# UNIDOCK_SIMPLE_2020-10-20_22-44-49.net
KiCad netlist of a schematic drawn in Altium Designer
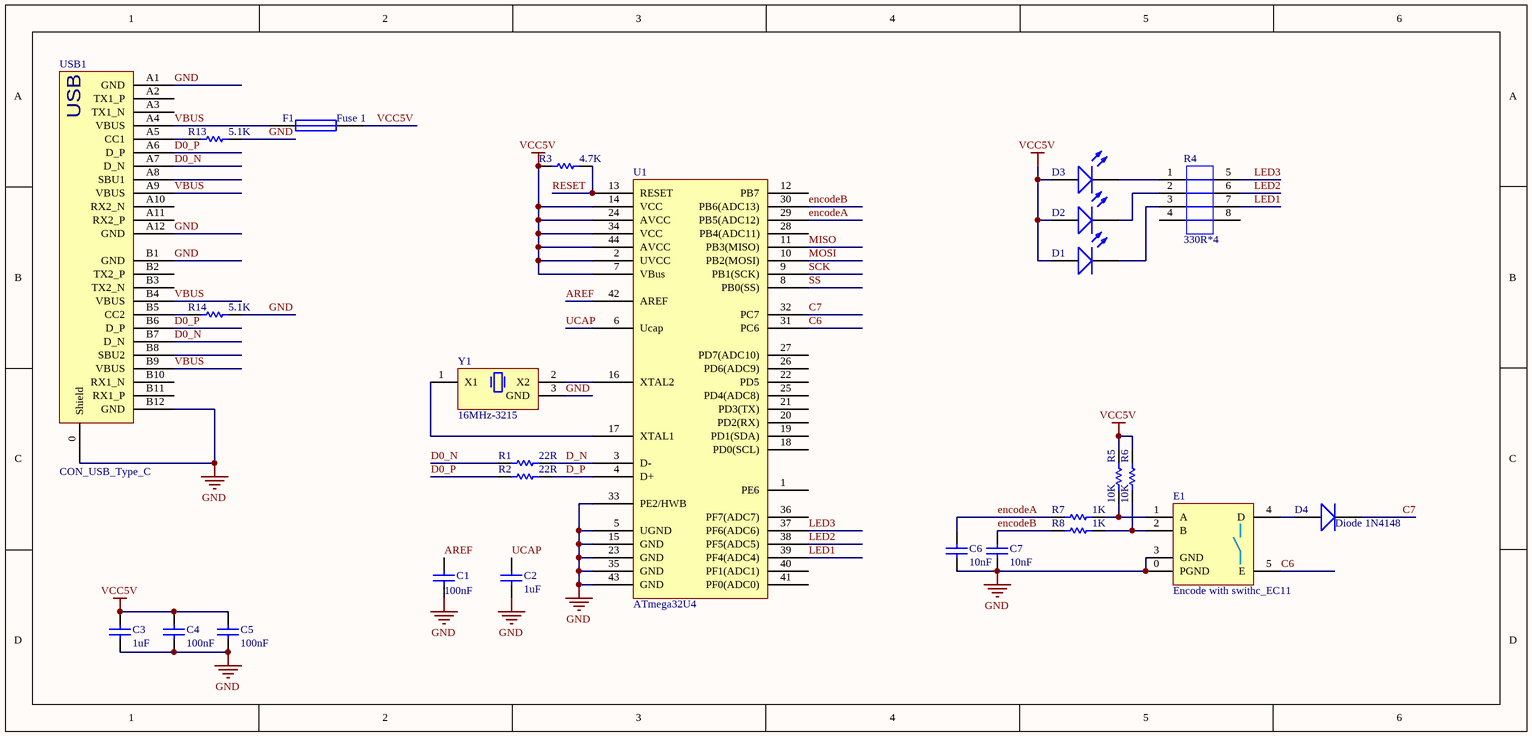
[diagram p0: UNIDOCK SIMPLE_2020-10-20_22-44-49.schdoc]

(export (version "E")
  (design (tool "Eeschema 10.0.6"))
  (components
    (comp (ref "C1")
      (value "100nF")
      (fields (field (name "PUBLISHER") "Altium Limited"))
      (libsource (lib "altium-import") (part "root_1_100nF_"))
    )
    (comp (ref "C2")
      (value "1uF")
      (fields (field (name "PUBLISHER") "Altium Limited"))
      (libsource (lib "altium-import") (part "root_3_1uF_"))
    )
    (comp (ref "C3")
      (value "1uF")
      (fields (field (name "PUBLISHER") "Altium Limited"))
      (libsource (lib "altium-import") (part "root_3_1uF_"))
    )
    (comp (ref "C4")
      (value "100nF")
      (fields (field (name "PUBLISHER") "Altium Limited"))
      (libsource (lib "altium-import") (part "root_3_100nF_"))
    )
    (comp (ref "C5")
      (value "100nF")
      (fields (field (name "PUBLISHER") "Altium Limited"))
      (libsource (lib "altium-import") (part "root_3_100nF_"))
    )
    (comp (ref "C6")
      (value "10nF")
      (fields (field (name "PUBLISHER") "Altium Limited"))
      (libsource (lib "altium-import") (part "root_1_10nF_"))
    )
    (comp (ref "C7")
      (value "10nF")
      (fields (field (name "PUBLISHER") "Altium Limited"))
      (libsource (lib "altium-import") (part "root_1_10nF_"))
    )
    (comp (ref "D1")
      (value "LED0")
      (fields (field (name "PUBLISHER") "Altium Limited"))
      (libsource (lib "altium-import") (part "root_0_LED0_"))
    )
    (comp (ref "D2")
      (value "LED0")
      (fields (field (name "PUBLISHER") "Altium Limited"))
      (libsource (lib "altium-import") (part "root_0_LED0_"))
    )
    (comp (ref "D3")
      (value "LED0")
      (fields (field (name "PUBLISHER") "Altium Limited"))
      (libsource (lib "altium-import") (part "root_0_LED0_"))
    )
    (comp (ref "D4")
      (value "Diode 1N4148")
      (fields (field (name "PUBLISHER") "Altium Limited"))
      (libsource (lib "altium-import") (part "root_0_Diode 1N4148_"))
    )
    (comp (ref "E1")
      (value "Encode with swithc_EC11")
      (libsource (lib "altium-import") (part "root_0_Encode with swithc_EC11_"))
    )
    (comp (ref "F1")
      (value "Fuse 1")
      (fields (field (name "PUBLISHER") "Altium Limited"))
      (libsource (lib "altium-import") (part "root_0_Fuse 1_"))
    )
    (comp (ref "R1")
      (value "22R")
      (fields (field (name "PUBLISHER") "Altium Limited"))
      (libsource (lib "altium-import") (part "root_2_22R_"))
    )
    (comp (ref "R2")
      (value "22R")
      (fields (field (name "PUBLISHER") "Altium Limited"))
      (libsource (lib "altium-import") (part "root_2_22R_"))
    )
    (comp (ref "R3")
      (value "4.7K")
      (fields (field (name "PUBLISHER") "Altium Limited"))
      (libsource (lib "altium-import") (part "root_0_4.7K_"))
    )
    (comp (ref "R4") (value "330R*4") (libsource (lib "altium-import") (part "root_0_330R*4_")))
    (comp (ref "R5")
      (value "10K")
      (fields (field (name "PUBLISHER") "Altium Limited"))
      (libsource (lib "altium-import") (part "root_1_10K_"))
    )
    (comp (ref "R6")
      (value "10K")
      (fields (field (name "PUBLISHER") "Altium Limited"))
      (libsource (lib "altium-import") (part "root_1_10K_"))
    )
    (comp (ref "R7")
      (value "1K")
      (fields (field (name "PUBLISHER") "Altium Limited"))
      (libsource (lib "altium-import") (part "root_0_1K_"))
    )
    (comp (ref "R8")
      (value "1K")
      (fields (field (name "PUBLISHER") "Altium Limited"))
      (libsource (lib "altium-import") (part "root_0_1K_"))
    )
    (comp (ref "R13")
      (value "5.1K")
      (fields (field (name "PUBLISHER") "Altium Limited"))
      (libsource (lib "altium-import") (part "root_0_5.1K_"))
    )
    (comp (ref "R14")
      (value "5.1K")
      (fields (field (name "PUBLISHER") "Altium Limited"))
      (libsource (lib "altium-import") (part "root_0_5.1K_"))
    )
    (comp (ref "U1") (value "ATmega32U4") (libsource (lib "altium-import") (part "root_0_ATmega32U4_")))
    (comp (ref "USB1")
      (value "CON_USB_Type_C")
      (libsource (lib "altium-import") (part "root_0_CON_USB_Type_C_"))
    )
    (comp (ref "Y1") (value "16MHz-3215") (libsource (lib "altium-import") (part "root_0_16MHz-3215_")))
  )
  (nets
    (net (code "1") (name "/AREF") (class "Default")
      (node (ref "C1") (pin "2") (pinfunction "2_2") (pintype "passive"))
      (node (ref "U1") (pin "42") (pinfunction "AREF_42") (pintype "passive"))
    )
    (net (code "2") (name "/C6") (class "Default")
      (node (ref "E1") (pin "5") (pinfunction "E_5") (pintype "passive"))
      (node (ref "U1") (pin "31") (pinfunction "PC6_31") (pintype "passive"))
    )
    (net (code "3") (name "/C7") (class "Default")
      (node (ref "D4") (pin "2") (pinfunction "K_2") (pintype "passive"))
      (node (ref "U1") (pin "32") (pinfunction "PC7_32") (pintype "passive"))
    )
    (net (code "4") (name "/D0_N") (class "Default")
      (node (ref "R1") (pin "2") (pinfunction "2_2") (pintype "passive"))
      (node (ref "USB1") (pin "A7") (pinfunction "D_N_A7") (pintype "passive"))
      (node (ref "USB1") (pin "B7") (pinfunction "D_N_B7") (pintype "passive"))
    )
    (net (code "5") (name "/D0_P") (class "Default")
      (node (ref "R2") (pin "2") (pinfunction "2_2") (pintype "passive"))
      (node (ref "USB1") (pin "A6") (pinfunction "D_P_A6") (pintype "passive"))
      (node (ref "USB1") (pin "B6") (pinfunction "D_P_B6") (pintype "passive"))
    )
    (net (code "6") (name "/D_N") (class "Default")
      (node (ref "R1") (pin "1") (pinfunction "1_1") (pintype "passive"))
      (node (ref "U1") (pin "3") (pinfunction "D-_3") (pintype "passive"))
    )
    (net (code "7") (name "/D_P") (class "Default")
      (node (ref "R2") (pin "1") (pinfunction "1_1") (pintype "passive"))
      (node (ref "U1") (pin "4") (pinfunction "D+_4") (pintype "passive"))
    )
    (net (code "8") (name "/LED1") (class "Default")
      (node (ref "R4") (pin "7") (pinfunction "7_7") (pintype "passive"))
      (node (ref "U1") (pin "39") (pinfunction "PF4(ADC4)_39") (pintype "passive"))
    )
    (net (code "9") (name "/LED2") (class "Default")
      (node (ref "R4") (pin "6") (pinfunction "6_6") (pintype "passive"))
      (node (ref "U1") (pin "38") (pinfunction "PF5(ADC5)_38") (pintype "passive"))
    )
    (net (code "10") (name "/LED3") (class "Default")
      (node (ref "R4") (pin "5") (pinfunction "5_5") (pintype "passive"))
      (node (ref "U1") (pin "37") (pinfunction "PF6(ADC6)_37") (pintype "passive"))
    )
    (net (code "11") (name "/MISO") (class "Default")
      (node (ref "U1") (pin "11") (pinfunction "PB3(MISO)_11") (pintype "passive"))
    )
    (net (code "12") (name "/MOSI") (class "Default")
      (node (ref "U1") (pin "10") (pinfunction "PB2(MOSI)_10") (pintype "passive"))
    )
    (net (code "13") (name "/RESET") (class "Default")
      (node (ref "R3") (pin "2") (pinfunction "2_2") (pintype "passive"))
      (node (ref "U1") (pin "13") (pinfunction "RESET_13") (pintype "passive"))
    )
    (net (code "14") (name "/SCK") (class "Default")
      (node (ref "U1") (pin "9") (pinfunction "PB1(SCK)_9") (pintype "passive"))
    )
    (net (code "15") (name "/SS") (class "Default")
      (node (ref "U1") (pin "8") (pinfunction "PB0(SS)_8") (pintype "passive"))
    )
    (net (code "16") (name "/UCAP") (class "Default")
      (node (ref "C2") (pin "1") (pinfunction "1_1") (pintype "passive"))
      (node (ref "U1") (pin "6") (pinfunction "Ucap_6") (pintype "passive"))
    )
    (net (code "17") (name "/VBUS") (class "Default")
      (node (ref "F1") (pin "1") (pinfunction "1_1") (pintype "passive"))
      (node (ref "USB1") (pin "A4") (pinfunction "VBUS_A4") (pintype "passive"))
      (node (ref "USB1") (pin "A9") (pinfunction "VBUS_A9") (pintype "passive"))
      (node (ref "USB1") (pin "B4") (pinfunction "VBUS_B4") (pintype "passive"))
      (node (ref "USB1") (pin "B9") (pinfunction "VBUS_B9") (pintype "passive"))
    )
    (net (code "18") (name "/encodeA") (class "Default")
      (node (ref "C6") (pin "2") (pinfunction "2_2") (pintype "passive"))
      (node (ref "R7") (pin "1") (pinfunction "1_1") (pintype "passive"))
      (node (ref "U1") (pin "29") (pinfunction "PB5(ADC12)_29") (pintype "passive"))
    )
    (net (code "19") (name "/encodeB") (class "Default")
      (node (ref "C7") (pin "2") (pinfunction "2_2") (pintype "passive"))
      (node (ref "R8") (pin "1") (pinfunction "1_1") (pintype "passive"))
      (node (ref "U1") (pin "30") (pinfunction "PB6(ADC13)_30") (pintype "passive"))
    )
    (net (code "20") (name "GND") (class "Default")
      (node (ref "C1") (pin "1") (pinfunction "1_1") (pintype "passive"))
      (node (ref "C2") (pin "2") (pinfunction "2_2") (pintype "passive"))
      (node (ref "C3") (pin "2") (pinfunction "2_2") (pintype "passive"))
      (node (ref "C4") (pin "2") (pinfunction "2_2") (pintype "passive"))
      (node (ref "C5") (pin "2") (pinfunction "2_2") (pintype "passive"))
      (node (ref "C6") (pin "1") (pinfunction "1_1") (pintype "passive"))
      (node (ref "C7") (pin "1") (pinfunction "1_1") (pintype "passive"))
      (node (ref "E1") (pin "0") (pinfunction "PGND_0") (pintype "passive"))
      (node (ref "E1") (pin "3") (pinfunction "GND_3") (pintype "passive"))
      (node (ref "R13") (pin "2") (pinfunction "2_2") (pintype "passive"))
      (node (ref "R14") (pin "2") (pinfunction "2_2") (pintype "passive"))
      (node (ref "U1") (pin "15") (pinfunction "GND_15") (pintype "passive"))
      (node (ref "U1") (pin "23") (pinfunction "GND_23") (pintype "passive"))
      (node (ref "U1") (pin "33") (pinfunction "PE2/HWB_33") (pintype "passive"))
      (node (ref "U1") (pin "35") (pinfunction "GND_35") (pintype "passive"))
      (node (ref "U1") (pin "43") (pinfunction "GND_43") (pintype "passive"))
      (node (ref "U1") (pin "5") (pinfunction "UGND_5") (pintype "passive"))
      (node (ref "USB1") (pin "0") (pinfunction "Shield_0") (pintype "passive"))
      (node (ref "USB1") (pin "A1") (pinfunction "GND_A1") (pintype "passive"))
      (node (ref "USB1") (pin "A12") (pinfunction "GND_A12") (pintype "passive"))
      (node (ref "USB1") (pin "B1") (pinfunction "GND_B1") (pintype "passive"))
      (node (ref "USB1") (pin "B12") (pinfunction "GND_B12") (pintype "passive"))
      (node (ref "Y1") (pin "3") (pinfunction "GND_3") (pintype "passive"))
    )
    (net (code "21") (name "Net-(D1-K)") (class "Default")
      (node (ref "D1") (pin "2") (pinfunction "K_2") (pintype "passive"))
      (node (ref "R4") (pin "3") (pinfunction "3_3") (pintype "passive"))
    )
    (net (code "22") (name "Net-(D2-K)") (class "Default")
      (node (ref "D2") (pin "2") (pinfunction "K_2") (pintype "passive"))
      (node (ref "R4") (pin "2") (pinfunction "2_2") (pintype "passive"))
    )
    (net (code "23") (name "Net-(D3-K)") (class "Default")
      (node (ref "D3") (pin "2") (pinfunction "K_2") (pintype "passive"))
      (node (ref "R4") (pin "1") (pinfunction "1_1") (pintype "passive"))
    )
    (net (code "24") (name "Net-(D4-A)") (class "Default")
      (node (ref "D4") (pin "1") (pinfunction "A_1") (pintype "passive"))
      (node (ref "E1") (pin "4") (pinfunction "D_4") (pintype "passive"))
    )
    (net (code "25") (name "Net-(E1-A)") (class "Default")
      (node (ref "E1") (pin "1") (pinfunction "A_1") (pintype "passive"))
      (node (ref "R5") (pin "1") (pinfunction "1_1") (pintype "passive"))
      (node (ref "R7") (pin "2") (pinfunction "2_2") (pintype "passive"))
    )
    (net (code "26") (name "Net-(E1-B)") (class "Default")
      (node (ref "E1") (pin "2") (pinfunction "B_2") (pintype "passive"))
      (node (ref "R6") (pin "1") (pinfunction "1_1") (pintype "passive"))
      (node (ref "R8") (pin "2") (pinfunction "2_2") (pintype "passive"))
    )
    (net (code "27") (name "Net-(U1-XTAL1)") (class "Default")
      (node (ref "U1") (pin "17") (pinfunction "XTAL1_17") (pintype "passive"))
      (node (ref "Y1") (pin "1") (pinfunction "X1_1") (pintype "passive"))
    )
    (net (code "28") (name "Net-(U1-XTAL2)") (class "Default")
      (node (ref "U1") (pin "16") (pinfunction "XTAL2_16") (pintype "passive"))
      (node (ref "Y1") (pin "2") (pinfunction "X2_2") (pintype "passive"))
    )
    (net (code "29") (name "Net-(USB1-CC1)") (class "Default")
      (node (ref "R13") (pin "1") (pinfunction "1_1") (pintype "passive"))
      (node (ref "USB1") (pin "A5") (pinfunction "CC1_A5") (pintype "passive"))
    )
    (net (code "30") (name "Net-(USB1-CC2)") (class "Default")
      (node (ref "R14") (pin "1") (pinfunction "1_1") (pintype "passive"))
      (node (ref "USB1") (pin "B5") (pinfunction "CC2_B5") (pintype "passive"))
    )
    (net (code "31") (name "VCC5V") (class "Default")
      (node (ref "C3") (pin "1") (pinfunction "1_1") (pintype "passive"))
      (node (ref "C4") (pin "1") (pinfunction "1_1") (pintype "passive"))
      (node (ref "C5") (pin "1") (pinfunction "1_1") (pintype "passive"))
      (node (ref "D1") (pin "1") (pinfunction "A_1") (pintype "passive"))
      (node (ref "D2") (pin "1") (pinfunction "A_1") (pintype "passive"))
      (node (ref "D3") (pin "1") (pinfunction "A_1") (pintype "passive"))
      (node (ref "F1") (pin "2") (pinfunction "2_2") (pintype "passive"))
      (node (ref "R3") (pin "1") (pinfunction "1_1") (pintype "passive"))
      (node (ref "R5") (pin "2") (pinfunction "2_2") (pintype "passive"))
      (node (ref "R6") (pin "2") (pinfunction "2_2") (pintype "passive"))
      (node (ref "U1") (pin "14") (pinfunction "VCC_14") (pintype "passive"))
      (node (ref "U1") (pin "2") (pinfunction "UVCC_2") (pintype "passive"))
      (node (ref "U1") (pin "24") (pinfunction "AVCC_24") (pintype "passive"))
      (node (ref "U1") (pin "34") (pinfunction "VCC_34") (pintype "passive"))
      (node (ref "U1") (pin "44") (pinfunction "AVCC_44") (pintype "passive"))
      (node (ref "U1") (pin "7") (pinfunction "VBus_7") (pintype "passive"))
    )
    (net (code "32") (name "unconnected-(R4-Pad4)") (class "Default")
      (node (ref "R4") (pin "4") (pinfunction "4_4") (pintype "passive"))
    )
    (net (code "33") (name "unconnected-(R4-Pad8)") (class "Default")
      (node (ref "R4") (pin "8") (pinfunction "8_8") (pintype "passive"))
    )
    (net (code "34") (name "unconnected-(U1-PB4(ADC11)-Pad28)") (class "Default")
      (node (ref "U1") (pin "28") (pinfunction "PB4(ADC11)_28") (pintype "passive"))
    )
    (net (code "35") (name "unconnected-(U1-PB7-Pad12)") (class "Default")
      (node (ref "U1") (pin "12") (pinfunction "PB7_12") (pintype "passive"))
    )
    (net (code "36") (name "unconnected-(U1-PD0(SCL)-Pad18)") (class "Default")
      (node (ref "U1") (pin "18") (pinfunction "PD0(SCL)_18") (pintype "passive"))
    )
    (net (code "37") (name "unconnected-(U1-PD1(SDA)-Pad19)") (class "Default")
      (node (ref "U1") (pin "19") (pinfunction "PD1(SDA)_19") (pintype "passive"))
    )
    (net (code "38") (name "unconnected-(U1-PD2(RX)-Pad20)") (class "Default")
      (node (ref "U1") (pin "20") (pinfunction "PD2(RX)_20") (pintype "passive"))
    )
    (net (code "39") (name "unconnected-(U1-PD3(TX)-Pad21)") (class "Default")
      (node (ref "U1") (pin "21") (pinfunction "PD3(TX)_21") (pintype "passive"))
    )
    (net (code "40") (name "unconnected-(U1-PD4(ADC8)-Pad25)") (class "Default")
      (node (ref "U1") (pin "25") (pinfunction "PD4(ADC8)_25") (pintype "passive"))
    )
    (net (code "41") (name "unconnected-(U1-PD5-Pad22)") (class "Default")
      (node (ref "U1") (pin "22") (pinfunction "PD5_22") (pintype "passive"))
    )
    (net (code "42") (name "unconnected-(U1-PD6(ADC9)-Pad26)") (class "Default")
      (node (ref "U1") (pin "26") (pinfunction "PD6(ADC9)_26") (pintype "passive"))
    )
    (net (code "43") (name "unconnected-(U1-PD7(ADC10)-Pad27)") (class "Default")
      (node (ref "U1") (pin "27") (pinfunction "PD7(ADC10)_27") (pintype "passive"))
    )
    (net (code "44") (name "unconnected-(U1-PE6-Pad1)") (class "Default")
      (node (ref "U1") (pin "1") (pinfunction "PE6_1") (pintype "passive"))
    )
    (net (code "45") (name "unconnected-(U1-PF0(ADC0)-Pad41)") (class "Default")
      (node (ref "U1") (pin "41") (pinfunction "PF0(ADC0)_41") (pintype "passive"))
    )
    (net (code "46") (name "unconnected-(U1-PF1(ADC1)-Pad40)") (class "Default")
      (node (ref "U1") (pin "40") (pinfunction "PF1(ADC1)_40") (pintype "passive"))
    )
    (net (code "47") (name "unconnected-(U1-PF7(ADC7)-Pad36)") (class "Default")
      (node (ref "U1") (pin "36") (pinfunction "PF7(ADC7)_36") (pintype "passive"))
    )
    (net (code "48") (name "unconnected-(USB1-RX1_N-PadB10)") (class "Default")
      (node (ref "USB1") (pin "B10") (pinfunction "RX1_N_B10") (pintype "passive"))
    )
    (net (code "49") (name "unconnected-(USB1-RX1_P-PadB11)") (class "Default")
      (node (ref "USB1") (pin "B11") (pinfunction "RX1_P_B11") (pintype "passive"))
    )
    (net (code "50") (name "unconnected-(USB1-RX2_N-PadA10)") (class "Default")
      (node (ref "USB1") (pin "A10") (pinfunction "RX2_N_A10") (pintype "passive"))
    )
    (net (code "51") (name "unconnected-(USB1-RX2_P-PadA11)") (class "Default")
      (node (ref "USB1") (pin "A11") (pinfunction "RX2_P_A11") (pintype "passive"))
    )
    (net (code "52") (name "unconnected-(USB1-SBU1-PadA8)") (class "Default")
      (node (ref "USB1") (pin "A8") (pinfunction "SBU1_A8") (pintype "passive"))
    )
    (net (code "53") (name "unconnected-(USB1-SBU2-PadB8)") (class "Default")
      (node (ref "USB1") (pin "B8") (pinfunction "SBU2_B8") (pintype "passive"))
    )
    (net (code "54") (name "unconnected-(USB1-TX1_N-PadA3)") (class "Default")
      (node (ref "USB1") (pin "A3") (pinfunction "TX1_N_A3") (pintype "passive"))
    )
    (net (code "55") (name "unconnected-(USB1-TX1_P-PadA2)") (class "Default")
      (node (ref "USB1") (pin "A2") (pinfunction "TX1_P_A2") (pintype "passive"))
    )
    (net (code "56") (name "unconnected-(USB1-TX2_N-PadB3)") (class "Default")
      (node (ref "USB1") (pin "B3") (pinfunction "TX2_N_B3") (pintype "passive"))
    )
    (net (code "57") (name "unconnected-(USB1-TX2_P-PadB2)") (class "Default")
      (node (ref "USB1") (pin "B2") (pinfunction "TX2_P_B2") (pintype "passive"))
    )
  )
)
